# tutisduino.net
KiCad netlist of a schematic drawn in EAGLE
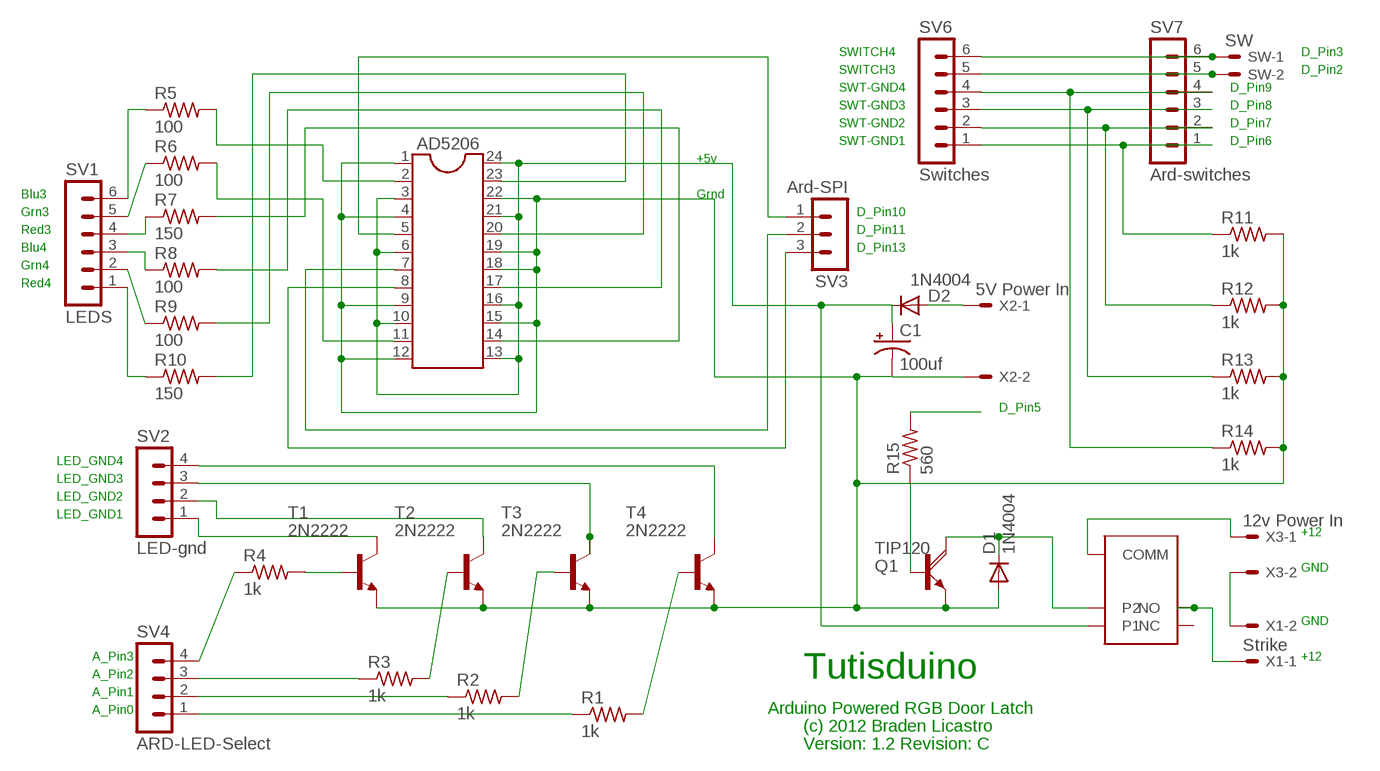
[diagram p0: schematic, sheet 1]

(export (version "E")
  (design (tool "Eeschema 10.0.6"))
  (components
    (comp (ref "AD5206")
      (value "DIL24-3")
      (footprint "eagle-import:DIL24-3")
      (libsource (lib "eagle-import") (part "DIL24-3"))
    )
    (comp (ref "C1")
      (value "100uf")
      (footprint "eagle-import:E2-5")
      (libsource (lib "eagle-import") (part "CPOL-USE2-5"))
    )
    (comp (ref "D1")
      (value "1N4004")
      (footprint "eagle-import:DO41-10")
      (libsource (lib "eagle-import") (part "1N4004"))
    )
    (comp (ref "D2")
      (value "1N4004")
      (footprint "eagle-import:DO41-10")
      (libsource (lib "eagle-import") (part "1N4004"))
    )
    (comp (ref "OUAZ-SS-105D")
      (value "OUAZ-SS-105D")
      (footprint "eagle-import:OUAZ-SS-105D")
      (libsource (lib "eagle-import") (part "OUAZ-SS-105D"))
    )
    (comp (ref "Q1")
      (value "TIP120")
      (footprint "eagle-import:TO220AH")
      (libsource (lib "eagle-import") (part "TIP120"))
    )
    (comp (ref "R1")
      (value "1k")
      (footprint "eagle-import:0204V")
      (libsource (lib "eagle-import") (part "R-US_0204/2V"))
    )
    (comp (ref "R2")
      (value "1k")
      (footprint "eagle-import:0204V")
      (libsource (lib "eagle-import") (part "R-US_0204/2V"))
    )
    (comp (ref "R3")
      (value "1k")
      (footprint "eagle-import:0204V")
      (libsource (lib "eagle-import") (part "R-US_0204/2V"))
    )
    (comp (ref "R4")
      (value "1k")
      (footprint "eagle-import:0204V")
      (libsource (lib "eagle-import") (part "R-US_0204/2V"))
    )
    (comp (ref "R5")
      (value "100")
      (footprint "eagle-import:0204V")
      (libsource (lib "eagle-import") (part "R-US_0204/2V"))
    )
    (comp (ref "R6")
      (value "100")
      (footprint "eagle-import:0204V")
      (libsource (lib "eagle-import") (part "R-US_0204/2V"))
    )
    (comp (ref "R7")
      (value "150")
      (footprint "eagle-import:0204V")
      (libsource (lib "eagle-import") (part "R-US_0204/2V"))
    )
    (comp (ref "R8")
      (value "100")
      (footprint "eagle-import:0204V")
      (libsource (lib "eagle-import") (part "R-US_0204/2V"))
    )
    (comp (ref "R9")
      (value "100")
      (footprint "eagle-import:0204V")
      (libsource (lib "eagle-import") (part "R-US_0204/2V"))
    )
    (comp (ref "R10")
      (value "150")
      (footprint "eagle-import:0204V")
      (libsource (lib "eagle-import") (part "R-US_0204/2V"))
    )
    (comp (ref "R11")
      (value "1k")
      (footprint "eagle-import:0204V")
      (libsource (lib "eagle-import") (part "R-US_0204/2V"))
    )
    (comp (ref "R12")
      (value "1k")
      (footprint "eagle-import:0204V")
      (libsource (lib "eagle-import") (part "R-US_0204/2V"))
    )
    (comp (ref "R13")
      (value "1k")
      (footprint "eagle-import:0204V")
      (libsource (lib "eagle-import") (part "R-US_0204/2V"))
    )
    (comp (ref "R14")
      (value "1k")
      (footprint "eagle-import:0204V")
      (libsource (lib "eagle-import") (part "R-US_0204/2V"))
    )
    (comp (ref "R15")
      (value "560")
      (footprint "eagle-import:0204V")
      (libsource (lib "eagle-import") (part "R-US_0204/2V"))
    )
    (comp (ref "SV1")
      (value "LEDS")
      (footprint "eagle-import:MA06-1")
      (libsource (lib "eagle-import") (part "MA06-1"))
    )
    (comp (ref "SV2")
      (value "LED-gnd")
      (footprint "eagle-import:MA04-1")
      (libsource (lib "eagle-import") (part "MA04-1"))
    )
    (comp (ref "SV3")
      (value "Ard-SPI")
      (footprint "eagle-import:MA03-1")
      (libsource (lib "eagle-import") (part "MA03-1"))
    )
    (comp (ref "SV4")
      (value "ARD-LED-Select")
      (footprint "eagle-import:MA04-1")
      (libsource (lib "eagle-import") (part "MA04-1"))
    )
    (comp (ref "SV6")
      (value "Switches")
      (footprint "eagle-import:MA06-1")
      (libsource (lib "eagle-import") (part "MA06-1"))
    )
    (comp (ref "SV7")
      (value "Ard-switches")
      (footprint "eagle-import:MA06-1")
      (libsource (lib "eagle-import") (part "MA06-1"))
    )
    (comp (ref "SW")
      (value "SW")
      (footprint "eagle-import:22-23-2021")
      (fields (field (name "MF") "MOLEX") (field (name "MPN") "22-23-2021"))
      (libsource (lib "eagle-import") (part "22-23-2021"))
    )
    (comp (ref "T1")
      (value "2N2222")
      (footprint "eagle-import:TO18")
      (libsource (lib "eagle-import") (part "2N2222"))
    )
    (comp (ref "T2")
      (value "2N2222")
      (footprint "eagle-import:TO18")
      (libsource (lib "eagle-import") (part "2N2222"))
    )
    (comp (ref "T3")
      (value "2N2222")
      (footprint "eagle-import:TO18")
      (libsource (lib "eagle-import") (part "2N2222"))
    )
    (comp (ref "T4")
      (value "2N2222")
      (footprint "eagle-import:TO18")
      (libsource (lib "eagle-import") (part "2N2222"))
    )
    (comp (ref "X1")
      (value "Strike")
      (footprint "eagle-import:22-23-2021")
      (fields (field (name "MF") "MOLEX") (field (name "MPN") "22-23-2021"))
      (libsource (lib "eagle-import") (part "22-23-2021"))
    )
    (comp (ref "X2")
      (value "5V Power In")
      (footprint "eagle-import:22-23-2021")
      (fields (field (name "MF") "MOLEX") (field (name "MPN") "22-23-2021"))
      (libsource (lib "eagle-import") (part "22-23-2021"))
    )
    (comp (ref "X3")
      (value "12v Power In")
      (footprint "eagle-import:22-23-2021")
      (fields (field (name "MF") "MOLEX") (field (name "MPN") "22-23-2021"))
      (libsource (lib "eagle-import") (part "22-23-2021"))
    )
  )
  (nets
    (net (code "1") (name "Net-(AD5206-Pad2)") (class "Default")
      (node (ref "AD5206") (pin "2") (pinfunction "2_2") (pintype "passive"))
      (node (ref "R5") (pin "2") (pinfunction "2_2") (pintype "passive"))
    )
    (net (code "2") (name "Net-(AD5206-Pad5)") (class "Default")
      (node (ref "AD5206") (pin "5") (pinfunction "5_5") (pintype "passive"))
      (node (ref "SV3") (pin "1") (pinfunction "1_1") (pintype "passive"))
    )
    (net (code "3") (name "Net-(AD5206-Pad7)") (class "Default")
      (node (ref "AD5206") (pin "7") (pinfunction "7_7") (pintype "passive"))
      (node (ref "SV3") (pin "2") (pinfunction "2_2") (pintype "passive"))
    )
    (net (code "4") (name "Net-(AD5206-Pad8)") (class "Default")
      (node (ref "AD5206") (pin "8") (pinfunction "8_8") (pintype "passive"))
      (node (ref "SV3") (pin "3") (pinfunction "3_3") (pintype "passive"))
    )
    (net (code "5") (name "Net-(AD5206-Pad10)") (class "Default")
      (node (ref "AD5206") (pin "10") (pinfunction "10_10") (pintype "passive"))
      (node (ref "AD5206") (pin "13") (pinfunction "13_13") (pintype "passive"))
      (node (ref "AD5206") (pin "16") (pinfunction "16_16") (pintype "passive"))
      (node (ref "AD5206") (pin "21") (pinfunction "21_21") (pintype "passive"))
      (node (ref "AD5206") (pin "24") (pinfunction "24_24") (pintype "passive"))
      (node (ref "AD5206") (pin "3") (pinfunction "3_3") (pintype "passive"))
      (node (ref "AD5206") (pin "6") (pinfunction "6_6") (pintype "passive"))
      (node (ref "C1") (pin "+") (pinfunction "+_+") (pintype "passive"))
      (node (ref "D2") (pin "C") (pinfunction "C_C") (pintype "passive"))
      (node (ref "OUAZ-SS-105D") (pin "P1") (pinfunction "P1_P1") (pintype "bidirectional"))
    )
    (net (code "6") (name "Net-(AD5206-Pad11)") (class "Default")
      (node (ref "AD5206") (pin "11") (pinfunction "11_11") (pintype "passive"))
      (node (ref "R6") (pin "2") (pinfunction "2_2") (pintype "passive"))
    )
    (net (code "7") (name "Net-(AD5206-Pad14)") (class "Default")
      (node (ref "AD5206") (pin "14") (pinfunction "14_14") (pintype "passive"))
      (node (ref "R7") (pin "2") (pinfunction "2_2") (pintype "passive"))
    )
    (net (code "8") (name "Net-(AD5206-Pad17)") (class "Default")
      (node (ref "AD5206") (pin "17") (pinfunction "17_17") (pintype "passive"))
      (node (ref "R8") (pin "2") (pinfunction "2_2") (pintype "passive"))
    )
    (net (code "9") (name "Net-(AD5206-Pad20)") (class "Default")
      (node (ref "AD5206") (pin "20") (pinfunction "20_20") (pintype "passive"))
      (node (ref "R9") (pin "2") (pinfunction "2_2") (pintype "passive"))
    )
    (net (code "10") (name "Net-(AD5206-Pad23)") (class "Default")
      (node (ref "AD5206") (pin "23") (pinfunction "23_23") (pintype "passive"))
      (node (ref "R10") (pin "2") (pinfunction "2_2") (pintype "passive"))
    )
    (net (code "11") (name "Net-(D1-PadC)") (class "Default")
      (node (ref "D1") (pin "C") (pinfunction "C_C") (pintype "passive"))
      (node (ref "OUAZ-SS-105D") (pin "P2") (pinfunction "P2_P2") (pintype "bidirectional"))
      (node (ref "Q1") (pin "C") (pinfunction "C_C") (pintype "passive"))
    )
    (net (code "12") (name "Net-(Q1-PadB)") (class "Default")
      (node (ref "Q1") (pin "B") (pinfunction "B_B") (pintype "passive"))
      (node (ref "R15") (pin "1") (pinfunction "1_1") (pintype "passive"))
    )
    (net (code "13") (name "Net-(R1-Pad1)") (class "Default")
      (node (ref "R1") (pin "1") (pinfunction "1_1") (pintype "passive"))
      (node (ref "SV4") (pin "1") (pinfunction "1_1") (pintype "passive"))
    )
    (net (code "14") (name "Net-(R2-Pad1)") (class "Default")
      (node (ref "R2") (pin "1") (pinfunction "1_1") (pintype "passive"))
      (node (ref "SV4") (pin "2") (pinfunction "2_2") (pintype "passive"))
    )
    (net (code "15") (name "Net-(R3-Pad1)") (class "Default")
      (node (ref "R3") (pin "1") (pinfunction "1_1") (pintype "passive"))
      (node (ref "SV4") (pin "3") (pinfunction "3_3") (pintype "passive"))
    )
    (net (code "16") (name "Net-(R4-Pad1)") (class "Default")
      (node (ref "R4") (pin "1") (pinfunction "1_1") (pintype "passive"))
      (node (ref "SV4") (pin "4") (pinfunction "4_4") (pintype "passive"))
    )
    (net (code "17") (name "Net-(R5-Pad1)") (class "Default")
      (node (ref "R5") (pin "1") (pinfunction "1_1") (pintype "passive"))
      (node (ref "SV1") (pin "6") (pinfunction "6_6") (pintype "passive"))
    )
    (net (code "18") (name "Net-(R6-Pad1)") (class "Default")
      (node (ref "R6") (pin "1") (pinfunction "1_1") (pintype "passive"))
      (node (ref "SV1") (pin "5") (pinfunction "5_5") (pintype "passive"))
    )
    (net (code "19") (name "Net-(R7-Pad1)") (class "Default")
      (node (ref "R7") (pin "1") (pinfunction "1_1") (pintype "passive"))
      (node (ref "SV1") (pin "4") (pinfunction "4_4") (pintype "passive"))
    )
    (net (code "20") (name "Net-(R8-Pad1)") (class "Default")
      (node (ref "R8") (pin "1") (pinfunction "1_1") (pintype "passive"))
      (node (ref "SV1") (pin "3") (pinfunction "3_3") (pintype "passive"))
    )
    (net (code "21") (name "Net-(R9-Pad1)") (class "Default")
      (node (ref "R9") (pin "1") (pinfunction "1_1") (pintype "passive"))
      (node (ref "SV1") (pin "2") (pinfunction "2_2") (pintype "passive"))
    )
    (net (code "22") (name "Net-(R10-Pad1)") (class "Default")
      (node (ref "R10") (pin "1") (pinfunction "1_1") (pintype "passive"))
      (node (ref "SV1") (pin "1") (pinfunction "1_1") (pintype "passive"))
    )
    (net (code "23") (name "Net-(R11-Pad1)") (class "Default")
      (node (ref "R11") (pin "1") (pinfunction "1_1") (pintype "passive"))
      (node (ref "SV6") (pin "1") (pinfunction "1_1") (pintype "passive"))
      (node (ref "SV7") (pin "1") (pinfunction "1_1") (pintype "passive"))
    )
    (net (code "24") (name "Net-(R12-Pad1)") (class "Default")
      (node (ref "R12") (pin "1") (pinfunction "1_1") (pintype "passive"))
      (node (ref "SV6") (pin "2") (pinfunction "2_2") (pintype "passive"))
      (node (ref "SV7") (pin "2") (pinfunction "2_2") (pintype "passive"))
    )
    (net (code "25") (name "Net-(R13-Pad1)") (class "Default")
      (node (ref "R13") (pin "1") (pinfunction "1_1") (pintype "passive"))
      (node (ref "SV6") (pin "3") (pinfunction "3_3") (pintype "passive"))
      (node (ref "SV7") (pin "3") (pinfunction "3_3") (pintype "passive"))
    )
    (net (code "26") (name "Net-(R14-Pad1)") (class "Default")
      (node (ref "R14") (pin "1") (pinfunction "1_1") (pintype "passive"))
      (node (ref "SV6") (pin "4") (pinfunction "4_4") (pintype "passive"))
      (node (ref "SV7") (pin "4") (pinfunction "4_4") (pintype "passive"))
    )
    (net (code "27") (name "Net-(SWA-S)") (class "Default")
      (node (ref "SV6") (pin "6") (pinfunction "6_6") (pintype "passive"))
      (node (ref "SV7") (pin "6") (pinfunction "6_6") (pintype "passive"))
      (node (ref "SW") (pin "1") (pinfunction "S_1") (pintype "passive"))
    )
    (net (code "28") (name "Net-(SWB-S)") (class "Default")
      (node (ref "SV6") (pin "5") (pinfunction "5_5") (pintype "passive"))
      (node (ref "SV7") (pin "5") (pinfunction "5_5") (pintype "passive"))
      (node (ref "SW") (pin "2") (pinfunction "S_2") (pintype "passive"))
    )
    (net (code "29") (name "Net-(T1-B)") (class "Default")
      (node (ref "R4") (pin "2") (pinfunction "2_2") (pintype "passive"))
      (node (ref "T1") (pin "2") (pinfunction "B_2") (pintype "passive"))
    )
    (net (code "30") (name "Net-(T1-C)") (class "Default")
      (node (ref "SV2") (pin "1") (pinfunction "1_1") (pintype "passive"))
      (node (ref "T1") (pin "3") (pinfunction "C_3") (pintype "passive"))
    )
    (net (code "31") (name "Net-(T1-E)") (class "Default")
      (node (ref "AD5206") (pin "1") (pinfunction "1_1") (pintype "passive"))
      (node (ref "AD5206") (pin "12") (pinfunction "12_12") (pintype "passive"))
      (node (ref "AD5206") (pin "15") (pinfunction "15_15") (pintype "passive"))
      (node (ref "AD5206") (pin "18") (pinfunction "18_18") (pintype "passive"))
      (node (ref "AD5206") (pin "19") (pinfunction "19_19") (pintype "passive"))
      (node (ref "AD5206") (pin "22") (pinfunction "22_22") (pintype "passive"))
      (node (ref "AD5206") (pin "4") (pinfunction "4_4") (pintype "passive"))
      (node (ref "AD5206") (pin "9") (pinfunction "9_9") (pintype "passive"))
      (node (ref "C1") (pin "-") (pinfunction "-_-") (pintype "passive"))
      (node (ref "D1") (pin "A") (pinfunction "A_A") (pintype "passive"))
      (node (ref "Q1") (pin "E") (pinfunction "E_E") (pintype "passive"))
      (node (ref "R11") (pin "2") (pinfunction "2_2") (pintype "passive"))
      (node (ref "R12") (pin "2") (pinfunction "2_2") (pintype "passive"))
      (node (ref "R13") (pin "2") (pinfunction "2_2") (pintype "passive"))
      (node (ref "R14") (pin "2") (pinfunction "2_2") (pintype "passive"))
      (node (ref "T1") (pin "1") (pinfunction "E_1") (pintype "passive"))
      (node (ref "T2") (pin "1") (pinfunction "E_1") (pintype "passive"))
      (node (ref "T3") (pin "1") (pinfunction "E_1") (pintype "passive"))
      (node (ref "T4") (pin "1") (pinfunction "E_1") (pintype "passive"))
      (node (ref "X2") (pin "2") (pinfunction "S_2") (pintype "passive"))
    )
    (net (code "32") (name "Net-(T2-B)") (class "Default")
      (node (ref "R3") (pin "2") (pinfunction "2_2") (pintype "passive"))
      (node (ref "T2") (pin "2") (pinfunction "B_2") (pintype "passive"))
    )
    (net (code "33") (name "Net-(T2-C)") (class "Default")
      (node (ref "SV2") (pin "2") (pinfunction "2_2") (pintype "passive"))
      (node (ref "T2") (pin "3") (pinfunction "C_3") (pintype "passive"))
    )
    (net (code "34") (name "Net-(T3-B)") (class "Default")
      (node (ref "R2") (pin "2") (pinfunction "2_2") (pintype "passive"))
      (node (ref "T3") (pin "2") (pinfunction "B_2") (pintype "passive"))
    )
    (net (code "35") (name "Net-(T3-C)") (class "Default")
      (node (ref "SV2") (pin "3") (pinfunction "3_3") (pintype "passive"))
      (node (ref "T3") (pin "3") (pinfunction "C_3") (pintype "passive"))
    )
    (net (code "36") (name "Net-(T4-B)") (class "Default")
      (node (ref "R1") (pin "2") (pinfunction "2_2") (pintype "passive"))
      (node (ref "T4") (pin "2") (pinfunction "B_2") (pintype "passive"))
    )
    (net (code "37") (name "Net-(T4-C)") (class "Default")
      (node (ref "SV2") (pin "4") (pinfunction "4_4") (pintype "passive"))
      (node (ref "T4") (pin "3") (pinfunction "C_3") (pintype "passive"))
    )
    (net (code "38") (name "Net-(X1A-S)") (class "Default")
      (node (ref "OUAZ-SS-105D") (pin "NO") (pinfunction "NO_NO") (pintype "bidirectional"))
      (node (ref "X1") (pin "1") (pinfunction "S_1") (pintype "passive"))
    )
    (net (code "39") (name "Net-(X1B-S)") (class "Default")
      (node (ref "X1") (pin "2") (pinfunction "S_2") (pintype "passive"))
      (node (ref "X3") (pin "2") (pinfunction "S_2") (pintype "passive"))
    )
    (net (code "40") (name "Net-(X2A-S)") (class "Default")
      (node (ref "D2") (pin "A") (pinfunction "A_A") (pintype "passive"))
      (node (ref "X2") (pin "1") (pinfunction "S_1") (pintype "passive"))
    )
    (net (code "41") (name "Net-(X3A-S)") (class "Default")
      (node (ref "OUAZ-SS-105D") (pin "COMM") (pinfunction "COMM_COMM") (pintype "bidirectional"))
      (node (ref "X3") (pin "1") (pinfunction "S_1") (pintype "passive"))
    )
    (net (code "42") (name "unconnected-(OUAZ-SS-105D-PadNC)") (class "Default")
      (node (ref "OUAZ-SS-105D") (pin "NC") (pinfunction "NC_NC") (pintype "bidirectional"))
    )
    (net (code "43") (name "unconnected-(R15-Pad2)") (class "Default")
      (node (ref "R15") (pin "2") (pinfunction "2_2") (pintype "passive"))
    )
  )
)
